# 03_Seven_Seg.net
KiCad netlist of a schematic drawn in Altium Designer
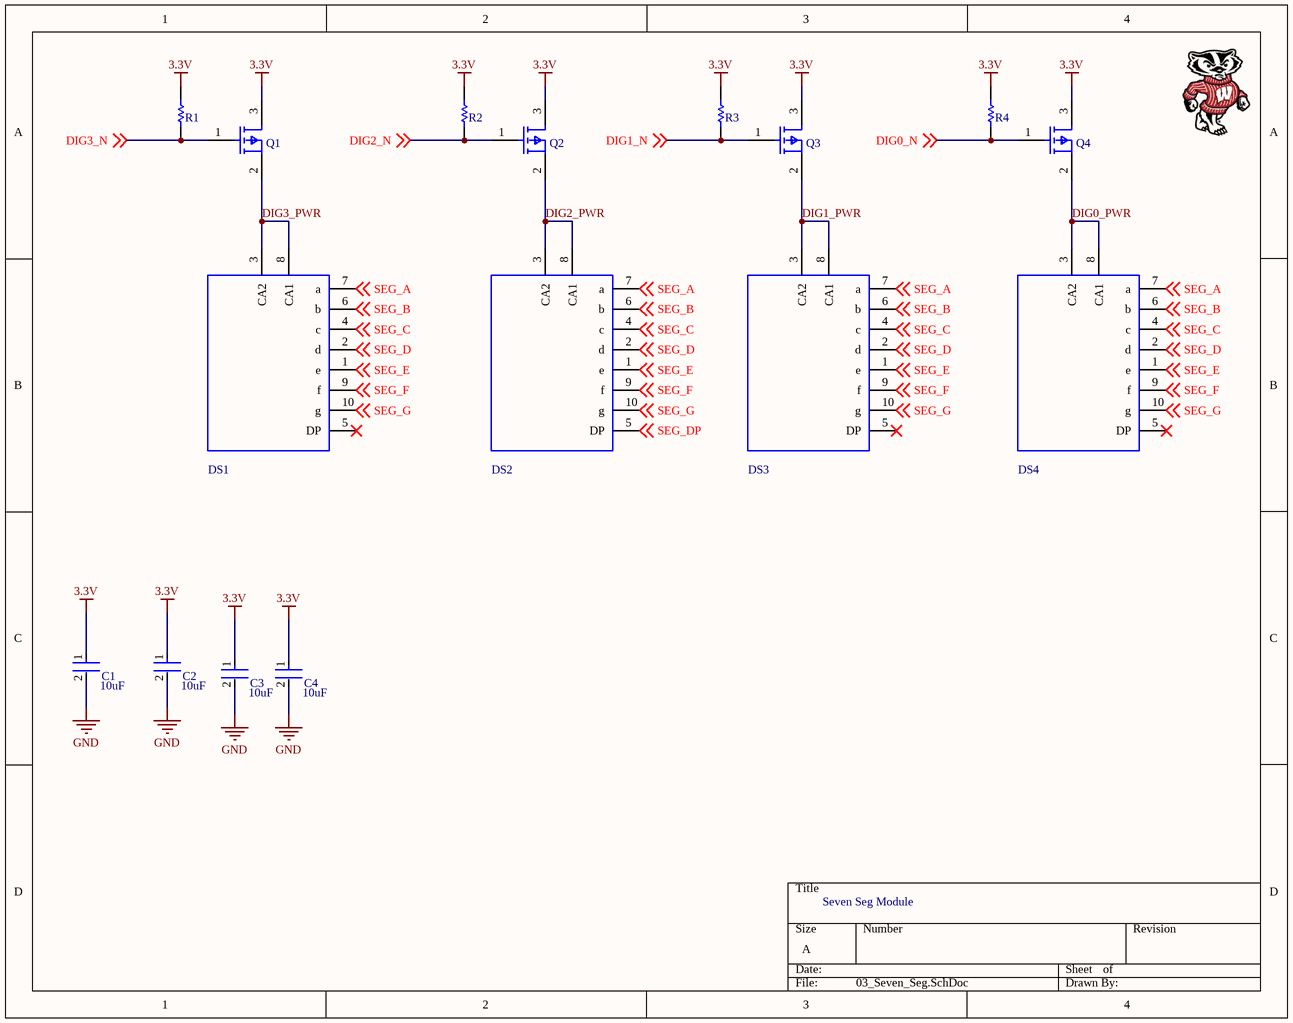
[diagram p0: 03_Seven_Seg.SchDoc]

(export (version "E")
  (design (tool "Eeschema 10.0.6"))
  (components
    (comp (ref "C1")
      (value "CL21A106KQCLNNC")
      (footprint "FP-CL21-IPC_B")
      (description "CL21 Series 0805 10uF 6.3V ±10% Tolerance X5R Multilayer Ceramic Chip Capacitor")
      (fields (field (name "CAPACITANCE") "10uF") (field (name "TOLERANCE") "10%"))
      (libsource (lib "Altium Content Vault") (part "b4654b650e69147ec39a6b967a45e02"))
    )
    (comp (ref "C2")
      (value "CL21A106KQCLNNC")
      (footprint "FP-CL21-IPC_B")
      (description "CL21 Series 0805 10uF 6.3V ±10% Tolerance X5R Multilayer Ceramic Chip Capacitor")
      (fields (field (name "CAPACITANCE") "10uF") (field (name "TOLERANCE") "10%"))
      (libsource (lib "Altium Content Vault") (part "b4654b650e69147ec39a6b967a45e02"))
    )
    (comp (ref "C3")
      (value "CL21A106KQCLNNC")
      (footprint "FP-CL21-IPC_B")
      (description "CL21 Series 0805 10uF 6.3V ±10% Tolerance X5R Multilayer Ceramic Chip Capacitor")
      (fields (field (name "CAPACITANCE") "10uF") (field (name "TOLERANCE") "10%"))
      (libsource (lib "Altium Content Vault") (part "b4654b650e69147ec39a6b967a45e02"))
    )
    (comp (ref "C4")
      (value "CL21A106KQCLNNC")
      (footprint "FP-CL21-IPC_B")
      (description "CL21 Series 0805 10uF 6.3V ±10% Tolerance X5R Multilayer Ceramic Chip Capacitor")
      (fields (field (name "CAPACITANCE") "10uF") (field (name "TOLERANCE") "10%"))
      (libsource (lib "Altium Content Vault") (part "b4654b650e69147ec39a6b967a45e02"))
    )
    (comp (ref "DS1")
      (value "ACSA56-41CGKWA-F01")
      (footprint "ACSA56-41CGKWA-F01")
      (description "DISPLAY 0.56\" SGL 574NM GRN SMD")
      (libsource (lib "team6") (part "ACSA56-41CGKWA-F01"))
    )
    (comp (ref "DS2")
      (value "ACSA56-41CGKWA-F01")
      (footprint "ACSA56-41CGKWA-F01")
      (description "DISPLAY 0.56\" SGL 574NM GRN SMD")
      (libsource (lib "team6") (part "ACSA56-41CGKWA-F01"))
    )
    (comp (ref "DS3")
      (value "ACSA56-41CGKWA-F01")
      (footprint "ACSA56-41CGKWA-F01")
      (description "DISPLAY 0.56\" SGL 574NM GRN SMD")
      (libsource (lib "team6") (part "ACSA56-41CGKWA-F01"))
    )
    (comp (ref "DS4")
      (value "ACSA56-41CGKWA-F01")
      (footprint "ACSA56-41CGKWA-F01")
      (description "DISPLAY 0.56\" SGL 574NM GRN SMD")
      (libsource (lib "team6") (part "ACSA56-41CGKWA-F01"))
    )
    (comp (ref "Q1")
      (value "SSM3J133TU")
      (footprint "UFM_TOS")
      (description "MOSFET P-CH 20V 4.4A UFM")
      (fields (field (name "COPYRIGHT") "Copyright (C) 2022 Ultra Librarian. All rights reserved."))
      (libsource (lib "team6") (part "SSM3J133TU"))
    )
    (comp (ref "Q2")
      (value "SSM3J133TU")
      (footprint "UFM_TOS")
      (description "MOSFET P-CH 20V 4.4A UFM")
      (fields (field (name "COPYRIGHT") "Copyright (C) 2022 Ultra Librarian. All rights reserved."))
      (libsource (lib "team6") (part "SSM3J133TU"))
    )
    (comp (ref "Q3")
      (value "SSM3J133TU")
      (footprint "UFM_TOS")
      (description "MOSFET P-CH 20V 4.4A UFM")
      (fields (field (name "COPYRIGHT") "Copyright (C) 2022 Ultra Librarian. All rights reserved."))
      (libsource (lib "team6") (part "SSM3J133TU"))
    )
    (comp (ref "Q4")
      (value "SSM3J133TU")
      (footprint "UFM_TOS")
      (description "MOSFET P-CH 20V 4.4A UFM")
      (fields (field (name "COPYRIGHT") "Copyright (C) 2022 Ultra Librarian. All rights reserved."))
      (libsource (lib "team6") (part "SSM3J133TU"))
    )
    (comp (ref "R1")
      (value "RES_0805_K_010.00")
      (footprint "RES_0805")
      (description "RES SMD 10K OHM 1% 1/8W 0805")
      (fields (field (name "TOLERANCE") "1%"))
      (libsource (lib "team6") (part "RES_0805_K_010.00"))
    )
    (comp (ref "R2")
      (value "RES_0805_K_010.00")
      (footprint "RES_0805")
      (description "RES SMD 10K OHM 1% 1/8W 0805")
      (fields (field (name "TOLERANCE") "1%"))
      (libsource (lib "team6") (part "RES_0805_K_010.00"))
    )
    (comp (ref "R3")
      (value "RES_0805_K_010.00")
      (footprint "RES_0805")
      (description "RES SMD 10K OHM 1% 1/8W 0805")
      (fields (field (name "TOLERANCE") "1%"))
      (libsource (lib "team6") (part "RES_0805_K_010.00"))
    )
    (comp (ref "R4")
      (value "RES_0805_K_010.00")
      (footprint "RES_0805")
      (description "RES SMD 10K OHM 1% 1/8W 0805")
      (fields (field (name "TOLERANCE") "1%"))
      (libsource (lib "team6") (part "RES_0805_K_010.00"))
    )
  )
  (nets
    (net (code "1") (name "/DIG0_PWR") (class "Default")
      (node (ref "DS4") (pin "3") (pinfunction "CA2_3") (pintype "passive"))
      (node (ref "DS4") (pin "8") (pinfunction "CA1_8") (pintype "passive"))
      (node (ref "Q4") (pin "2") (pinfunction "Source_2") (pintype "passive"))
    )
    (net (code "2") (name "/DIG1_PWR") (class "Default")
      (node (ref "DS3") (pin "3") (pinfunction "CA2_3") (pintype "passive"))
      (node (ref "DS3") (pin "8") (pinfunction "CA1_8") (pintype "passive"))
      (node (ref "Q3") (pin "2") (pinfunction "Source_2") (pintype "passive"))
    )
    (net (code "3") (name "/DIG2_PWR") (class "Default")
      (node (ref "DS2") (pin "3") (pinfunction "CA2_3") (pintype "passive"))
      (node (ref "DS2") (pin "8") (pinfunction "CA1_8") (pintype "passive"))
      (node (ref "Q2") (pin "2") (pinfunction "Source_2") (pintype "passive"))
    )
    (net (code "4") (name "/DIG3_PWR") (class "Default")
      (node (ref "DS1") (pin "3") (pinfunction "CA2_3") (pintype "passive"))
      (node (ref "DS1") (pin "8") (pinfunction "CA1_8") (pintype "passive"))
      (node (ref "Q1") (pin "2") (pinfunction "Source_2") (pintype "passive"))
    )
    (net (code "5") (name "3.3V") (class "Default")
      (node (ref "C1") (pin "1") (pinfunction "1_1") (pintype "passive"))
      (node (ref "C2") (pin "1") (pinfunction "1_1") (pintype "passive"))
      (node (ref "C3") (pin "1") (pinfunction "1_1") (pintype "passive"))
      (node (ref "C4") (pin "1") (pinfunction "1_1") (pintype "passive"))
      (node (ref "Q1") (pin "3") (pinfunction "Drain_3") (pintype "passive"))
      (node (ref "Q2") (pin "3") (pinfunction "Drain_3") (pintype "passive"))
      (node (ref "Q3") (pin "3") (pinfunction "Drain_3") (pintype "passive"))
      (node (ref "Q4") (pin "3") (pinfunction "Drain_3") (pintype "passive"))
      (node (ref "R1") (pin "2") (pinfunction "2_2") (pintype "passive"))
      (node (ref "R2") (pin "2") (pinfunction "2_2") (pintype "passive"))
      (node (ref "R3") (pin "2") (pinfunction "2_2") (pintype "passive"))
      (node (ref "R4") (pin "2") (pinfunction "2_2") (pintype "passive"))
    )
    (net (code "6") (name "DIG0_N") (class "Default")
      (node (ref "Q4") (pin "1") (pinfunction "Gate_1") (pintype "passive"))
      (node (ref "R4") (pin "1") (pinfunction "1_1") (pintype "passive"))
    )
    (net (code "7") (name "DIG1_N") (class "Default")
      (node (ref "Q3") (pin "1") (pinfunction "Gate_1") (pintype "passive"))
      (node (ref "R3") (pin "1") (pinfunction "1_1") (pintype "passive"))
    )
    (net (code "8") (name "DIG2_N") (class "Default")
      (node (ref "Q2") (pin "1") (pinfunction "Gate_1") (pintype "passive"))
      (node (ref "R2") (pin "1") (pinfunction "1_1") (pintype "passive"))
    )
    (net (code "9") (name "DIG3_N") (class "Default")
      (node (ref "Q1") (pin "1") (pinfunction "Gate_1") (pintype "passive"))
      (node (ref "R1") (pin "1") (pinfunction "1_1") (pintype "passive"))
    )
    (net (code "10") (name "GND") (class "Default")
      (node (ref "C1") (pin "2") (pinfunction "2_2") (pintype "passive"))
      (node (ref "C2") (pin "2") (pinfunction "2_2") (pintype "passive"))
      (node (ref "C3") (pin "2") (pinfunction "2_2") (pintype "passive"))
      (node (ref "C4") (pin "2") (pinfunction "2_2") (pintype "passive"))
    )
    (net (code "11") (name "SEG_A") (class "Default")
      (node (ref "DS1") (pin "7") (pinfunction "a_7") (pintype "passive"))
      (node (ref "DS2") (pin "7") (pinfunction "a_7") (pintype "passive"))
      (node (ref "DS3") (pin "7") (pinfunction "a_7") (pintype "passive"))
      (node (ref "DS4") (pin "7") (pinfunction "a_7") (pintype "passive"))
    )
    (net (code "12") (name "SEG_B") (class "Default")
      (node (ref "DS1") (pin "6") (pinfunction "b_6") (pintype "passive"))
      (node (ref "DS2") (pin "6") (pinfunction "b_6") (pintype "passive"))
      (node (ref "DS3") (pin "6") (pinfunction "b_6") (pintype "passive"))
      (node (ref "DS4") (pin "6") (pinfunction "b_6") (pintype "passive"))
    )
    (net (code "13") (name "SEG_C") (class "Default")
      (node (ref "DS1") (pin "4") (pinfunction "c_4") (pintype "passive"))
      (node (ref "DS2") (pin "4") (pinfunction "c_4") (pintype "passive"))
      (node (ref "DS3") (pin "4") (pinfunction "c_4") (pintype "passive"))
      (node (ref "DS4") (pin "4") (pinfunction "c_4") (pintype "passive"))
    )
    (net (code "14") (name "SEG_D") (class "Default")
      (node (ref "DS1") (pin "2") (pinfunction "d_2") (pintype "passive"))
      (node (ref "DS2") (pin "2") (pinfunction "d_2") (pintype "passive"))
      (node (ref "DS3") (pin "2") (pinfunction "d_2") (pintype "passive"))
      (node (ref "DS4") (pin "2") (pinfunction "d_2") (pintype "passive"))
    )
    (net (code "15") (name "SEG_DP") (class "Default")
      (node (ref "DS2") (pin "5") (pinfunction "DP_5") (pintype "passive"))
    )
    (net (code "16") (name "SEG_E") (class "Default")
      (node (ref "DS1") (pin "1") (pinfunction "e_1") (pintype "passive"))
      (node (ref "DS2") (pin "1") (pinfunction "e_1") (pintype "passive"))
      (node (ref "DS3") (pin "1") (pinfunction "e_1") (pintype "passive"))
      (node (ref "DS4") (pin "1") (pinfunction "e_1") (pintype "passive"))
    )
    (net (code "17") (name "SEG_F") (class "Default")
      (node (ref "DS1") (pin "9") (pinfunction "f_9") (pintype "passive"))
      (node (ref "DS2") (pin "9") (pinfunction "f_9") (pintype "passive"))
      (node (ref "DS3") (pin "9") (pinfunction "f_9") (pintype "passive"))
      (node (ref "DS4") (pin "9") (pinfunction "f_9") (pintype "passive"))
    )
    (net (code "18") (name "SEG_G") (class "Default")
      (node (ref "DS1") (pin "10") (pinfunction "g_10") (pintype "passive"))
      (node (ref "DS2") (pin "10") (pinfunction "g_10") (pintype "passive"))
      (node (ref "DS3") (pin "10") (pinfunction "g_10") (pintype "passive"))
      (node (ref "DS4") (pin "10") (pinfunction "g_10") (pintype "passive"))
    )
    (net (code "19") (name "unconnected-(DS1-DP-Pad5)") (class "Default")
      (node (ref "DS1") (pin "5") (pinfunction "DP_5") (pintype "passive+no_connect"))
    )
    (net (code "20") (name "unconnected-(DS3-DP-Pad5)") (class "Default")
      (node (ref "DS3") (pin "5") (pinfunction "DP_5") (pintype "passive+no_connect"))
    )
    (net (code "21") (name "unconnected-(DS4-DP-Pad5)") (class "Default")
      (node (ref "DS4") (pin "5") (pinfunction "DP_5") (pintype "passive+no_connect"))
    )
  )
)
